# V1.net
KiCad netlist of a schematic drawn in EAGLE
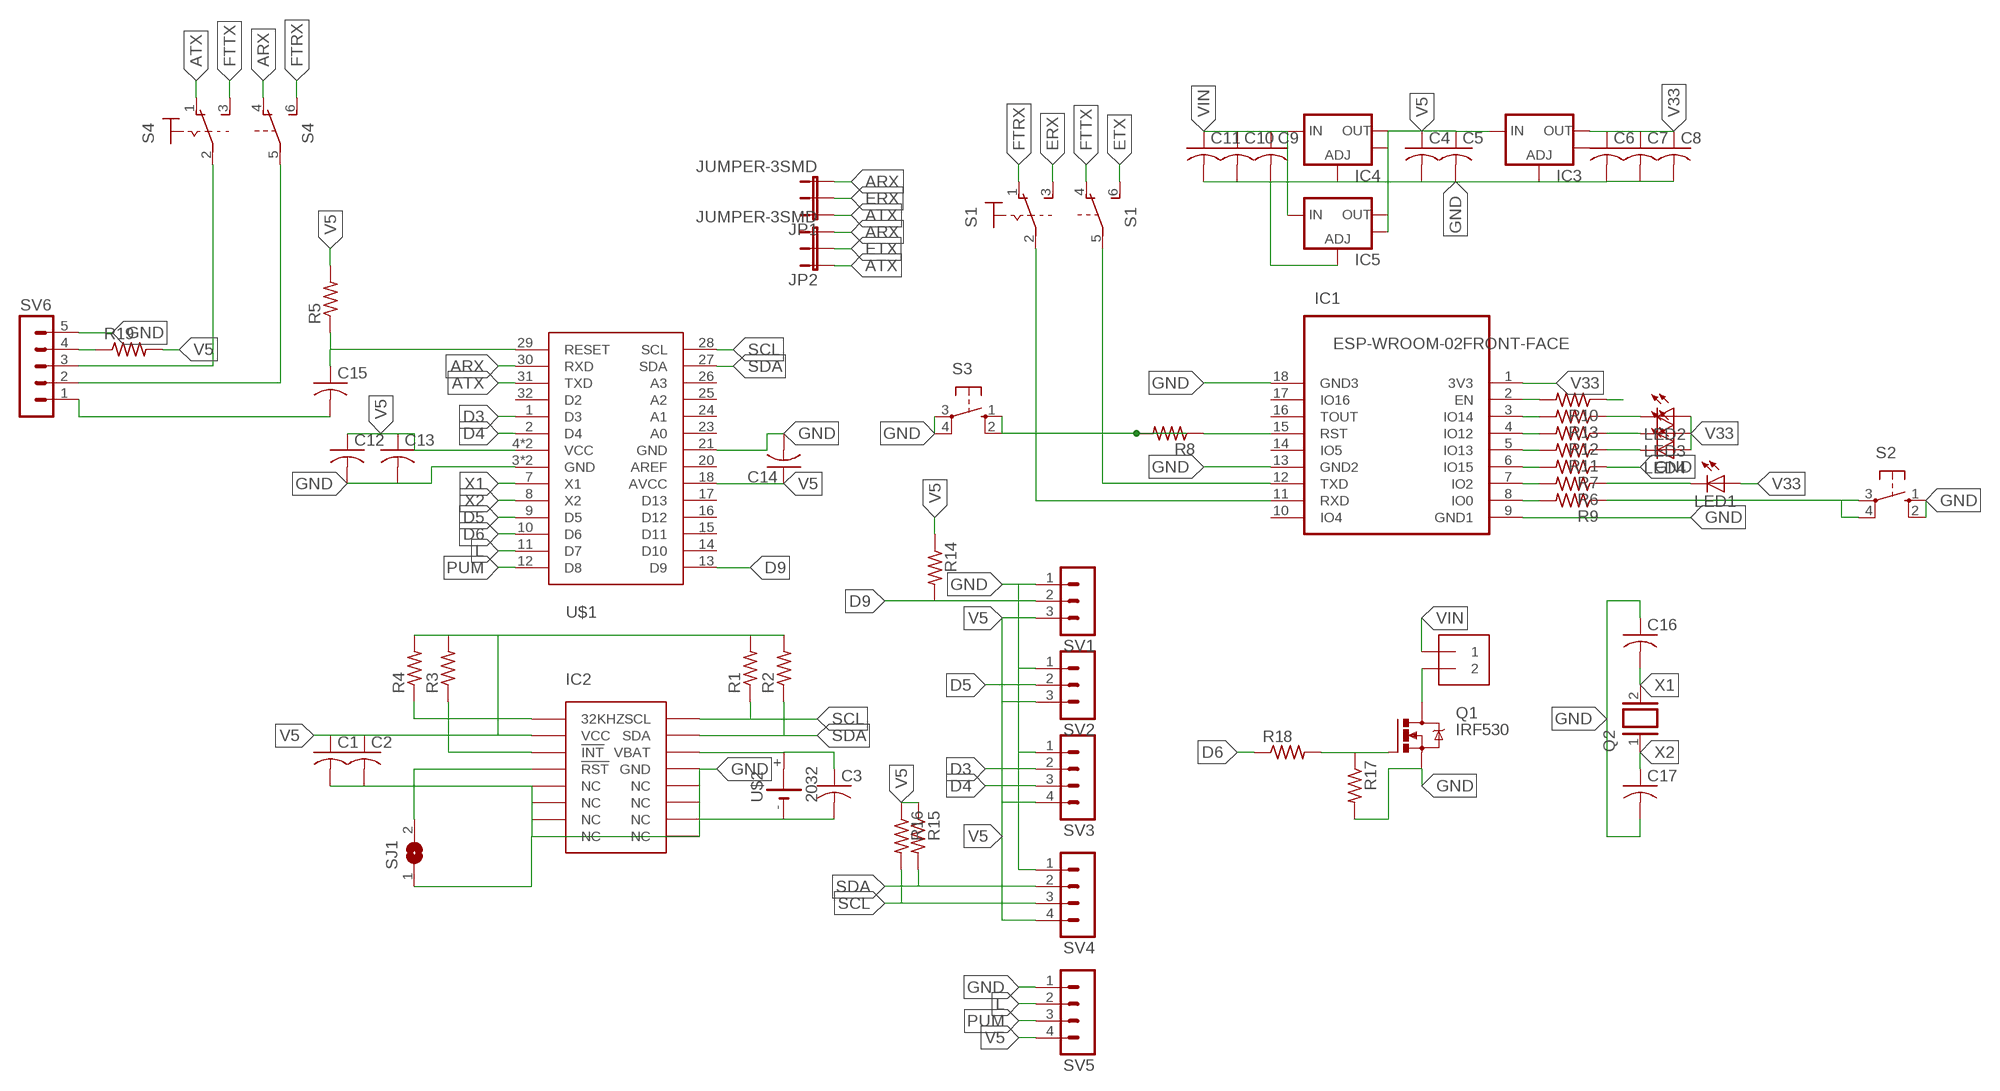
[diagram p0: schematic, sheet 1]

(export (version "E")
  (design (tool "Eeschema 10.0.6"))
  (components
    (comp (ref "C1")
      (value "C-USC0805")
      (footprint "eagle-import:C0805")
      (libsource (lib "eagle-import") (part "C-USC0805"))
    )
    (comp (ref "C2")
      (value "C-USC0805")
      (footprint "eagle-import:C0805")
      (libsource (lib "eagle-import") (part "C-USC0805"))
    )
    (comp (ref "C3")
      (value "C-USC0805")
      (footprint "eagle-import:C0805")
      (libsource (lib "eagle-import") (part "C-USC0805"))
    )
    (comp (ref "C4")
      (value "C-USC0805")
      (footprint "eagle-import:C0805")
      (libsource (lib "eagle-import") (part "C-USC0805"))
    )
    (comp (ref "C5")
      (value "C-USC0805")
      (footprint "eagle-import:C0805")
      (libsource (lib "eagle-import") (part "C-USC0805"))
    )
    (comp (ref "C6")
      (value "C-USC0805")
      (footprint "eagle-import:C0805")
      (libsource (lib "eagle-import") (part "C-USC0805"))
    )
    (comp (ref "C7")
      (value "C-USC0805")
      (footprint "eagle-import:C0805")
      (libsource (lib "eagle-import") (part "C-USC0805"))
    )
    (comp (ref "C8")
      (value "C-USC0805")
      (footprint "eagle-import:C0805")
      (libsource (lib "eagle-import") (part "C-USC0805"))
    )
    (comp (ref "C9")
      (value "C-USC0805")
      (footprint "eagle-import:C0805")
      (libsource (lib "eagle-import") (part "C-USC0805"))
    )
    (comp (ref "C10")
      (value "C-USC0805")
      (footprint "eagle-import:C0805")
      (libsource (lib "eagle-import") (part "C-USC0805"))
    )
    (comp (ref "C11")
      (value "C-USC0805")
      (footprint "eagle-import:C0805")
      (libsource (lib "eagle-import") (part "C-USC0805"))
    )
    (comp (ref "C12")
      (value "C-USC0805")
      (footprint "eagle-import:C0805")
      (libsource (lib "eagle-import") (part "C-USC0805"))
    )
    (comp (ref "C13")
      (value "C-USC0805")
      (footprint "eagle-import:C0805")
      (libsource (lib "eagle-import") (part "C-USC0805"))
    )
    (comp (ref "C14")
      (value "C-USC0805")
      (footprint "eagle-import:C0805")
      (libsource (lib "eagle-import") (part "C-USC0805"))
    )
    (comp (ref "C15")
      (value "C-USC0805")
      (footprint "eagle-import:C0805")
      (libsource (lib "eagle-import") (part "C-USC0805"))
    )
    (comp (ref "C16")
      (value "C-USC0805")
      (footprint "eagle-import:C0805")
      (libsource (lib "eagle-import") (part "C-USC0805"))
    )
    (comp (ref "C17")
      (value "C-USC0805")
      (footprint "eagle-import:C0805")
      (libsource (lib "eagle-import") (part "C-USC0805"))
    )
    (comp (ref "IC1")
      (value "ESP-WROOM-02FRONT-FACE")
      (footprint "eagle-import:FRONT-FACE")
      (libsource (lib "eagle-import") (part "ESP-WROOM-02FRONT-FACE"))
    )
    (comp (ref "IC2")
      (value "DS3231SOIC-16W")
      (footprint "eagle-import:SOIC-16W")
      (libsource (lib "eagle-import") (part "DS3231SOIC-16W"))
    )
    (comp (ref "IC3")
      (value "V_REG_LM1117SOT223")
      (footprint "eagle-import:SOT223")
      (libsource (lib "eagle-import") (part "V_REG_LM1117SOT223"))
    )
    (comp (ref "IC4")
      (value "V_REG_LM1117SOT223")
      (footprint "eagle-import:SOT223")
      (libsource (lib "eagle-import") (part "V_REG_LM1117SOT223"))
    )
    (comp (ref "IC5")
      (value "V_REG_LM1117SOT223")
      (footprint "eagle-import:SOT223")
      (libsource (lib "eagle-import") (part "V_REG_LM1117SOT223"))
    )
    (comp (ref "J1")
      (value "1X2-3.5MM")
      (footprint "eagle-import:3.5MMTERM")
      (libsource (lib "eagle-import") (part "1X2-3.5MM"))
    )
    (comp (ref "JP1")
      (value "JUMPER-3SMD")
      (footprint "eagle-import:SJ_3")
      (libsource (lib "eagle-import") (part "JUMPER-3SMD"))
    )
    (comp (ref "JP2")
      (value "JUMPER-3SMD")
      (footprint "eagle-import:SJ_3")
      (libsource (lib "eagle-import") (part "JUMPER-3SMD"))
    )
    (comp (ref "LED1")
      (value "LED5MM")
      (footprint "eagle-import:LED5MM")
      (libsource (lib "eagle-import") (part "LED5MM"))
    )
    (comp (ref "LED2")
      (value "LED5MM")
      (footprint "eagle-import:LED5MM")
      (libsource (lib "eagle-import") (part "LED5MM"))
    )
    (comp (ref "LED3")
      (value "LED5MM")
      (footprint "eagle-import:LED5MM")
      (libsource (lib "eagle-import") (part "LED5MM"))
    )
    (comp (ref "LED4")
      (value "LED5MM")
      (footprint "eagle-import:LED5MM")
      (libsource (lib "eagle-import") (part "LED5MM"))
    )
    (comp (ref "Q1")
      (value "IRF530")
      (footprint "eagle-import:TO220BV")
      (libsource (lib "eagle-import") (part "IRF530"))
    )
    (comp (ref "Q2")
      (value "XTAL/S")
      (footprint "eagle-import:QS")
      (libsource (lib "eagle-import") (part "XTAL/S"))
    )
    (comp (ref "R1")
      (value "R-US_R0805")
      (footprint "eagle-import:R0805")
      (libsource (lib "eagle-import") (part "R-US_R0805"))
    )
    (comp (ref "R2")
      (value "R-US_R0805")
      (footprint "eagle-import:R0805")
      (libsource (lib "eagle-import") (part "R-US_R0805"))
    )
    (comp (ref "R3")
      (value "R-US_R0805")
      (footprint "eagle-import:R0805")
      (libsource (lib "eagle-import") (part "R-US_R0805"))
    )
    (comp (ref "R4")
      (value "R-US_R0805")
      (footprint "eagle-import:R0805")
      (libsource (lib "eagle-import") (part "R-US_R0805"))
    )
    (comp (ref "R5")
      (value "R-US_R0805")
      (footprint "eagle-import:R0805")
      (libsource (lib "eagle-import") (part "R-US_R0805"))
    )
    (comp (ref "R6")
      (value "R-US_R0805")
      (footprint "eagle-import:R0805")
      (libsource (lib "eagle-import") (part "R-US_R0805"))
    )
    (comp (ref "R7")
      (value "R-US_R0805")
      (footprint "eagle-import:R0805")
      (libsource (lib "eagle-import") (part "R-US_R0805"))
    )
    (comp (ref "R8")
      (value "R-US_R0805")
      (footprint "eagle-import:R0805")
      (libsource (lib "eagle-import") (part "R-US_R0805"))
    )
    (comp (ref "R9")
      (value "R-US_R0805")
      (footprint "eagle-import:R0805")
      (libsource (lib "eagle-import") (part "R-US_R0805"))
    )
    (comp (ref "R10")
      (value "R-US_R0805")
      (footprint "eagle-import:R0805")
      (libsource (lib "eagle-import") (part "R-US_R0805"))
    )
    (comp (ref "R11")
      (value "R-US_R0805")
      (footprint "eagle-import:R0805")
      (libsource (lib "eagle-import") (part "R-US_R0805"))
    )
    (comp (ref "R12")
      (value "R-US_R0805")
      (footprint "eagle-import:R0805")
      (libsource (lib "eagle-import") (part "R-US_R0805"))
    )
    (comp (ref "R13")
      (value "R-US_R0805")
      (footprint "eagle-import:R0805")
      (libsource (lib "eagle-import") (part "R-US_R0805"))
    )
    (comp (ref "R14")
      (value "R-US_R0805")
      (footprint "eagle-import:R0805")
      (libsource (lib "eagle-import") (part "R-US_R0805"))
    )
    (comp (ref "R15")
      (value "R-US_R0805")
      (footprint "eagle-import:R0805")
      (libsource (lib "eagle-import") (part "R-US_R0805"))
    )
    (comp (ref "R16")
      (value "R-US_R0805")
      (footprint "eagle-import:R0805")
      (libsource (lib "eagle-import") (part "R-US_R0805"))
    )
    (comp (ref "R17")
      (value "R-US_R0805")
      (footprint "eagle-import:R0805")
      (libsource (lib "eagle-import") (part "R-US_R0805"))
    )
    (comp (ref "R18")
      (value "R-US_R0805")
      (footprint "eagle-import:R0805")
      (libsource (lib "eagle-import") (part "R-US_R0805"))
    )
    (comp (ref "R19")
      (value "R-US_R0805")
      (footprint "eagle-import:R0805")
      (libsource (lib "eagle-import") (part "R-US_R0805"))
    )
    (comp (ref "S1")
      (value "320-938")
      (footprint "eagle-import:320-938")
      (libsource (lib "eagle-import") (part "320-938"))
    )
    (comp (ref "S2")
      (value "10-XX")
      (footprint "eagle-import:B3F-10XX")
      (fields (field (name "MPN") "B3F-1000"))
      (libsource (lib "eagle-import") (part "10-XX"))
    )
    (comp (ref "S3")
      (value "10-XX")
      (footprint "eagle-import:B3F-10XX")
      (fields (field (name "MPN") "B3F-1000"))
      (libsource (lib "eagle-import") (part "10-XX"))
    )
    (comp (ref "S4")
      (value "320-938")
      (footprint "eagle-import:320-938")
      (libsource (lib "eagle-import") (part "320-938"))
    )
    (comp (ref "SJ1")
      (value "SJW")
      (footprint "eagle-import:SJW")
      (libsource (lib "eagle-import") (part "SJW"))
    )
    (comp (ref "SV1")
      (value "MA03-1")
      (footprint "eagle-import:MA03-1")
      (libsource (lib "eagle-import") (part "MA03-1"))
    )
    (comp (ref "SV2")
      (value "MA03-1")
      (footprint "eagle-import:MA03-1")
      (libsource (lib "eagle-import") (part "MA03-1"))
    )
    (comp (ref "SV3")
      (value "MA04-1")
      (footprint "eagle-import:MA04-1")
      (libsource (lib "eagle-import") (part "MA04-1"))
    )
    (comp (ref "SV4")
      (value "MA04-1")
      (footprint "eagle-import:MA04-1")
      (libsource (lib "eagle-import") (part "MA04-1"))
    )
    (comp (ref "SV5")
      (value "MA04-1")
      (footprint "eagle-import:MA04-1")
      (libsource (lib "eagle-import") (part "MA04-1"))
    )
    (comp (ref "SV6")
      (value "MA05-1")
      (footprint "eagle-import:MA05-1")
      (libsource (lib "eagle-import") (part "MA05-1"))
    )
    (comp (ref "U$1")
      (value "ATMEGA328P")
      (footprint "eagle-import:TQFP32-08")
      (libsource (lib "eagle-import") (part "ATMEGA328P"))
    )
    (comp (ref "U$2")
      (value "2032")
      (footprint "eagle-import:KZH20SMD")
      (libsource (lib "eagle-import") (part "2032"))
    )
  )
  (nets
    (net (code "1") (name "ARX") (class "Default")
      (node (ref "C15") (pin "1") (pinfunction "1_1") (pintype "passive"))
      (node (ref "JP1") (pin "3") (pinfunction "3_3") (pintype "passive"))
      (node (ref "JP2") (pin "3") (pinfunction "3_3") (pintype "passive"))
      (node (ref "R5") (pin "1") (pinfunction "1_1") (pintype "passive"))
      (node (ref "S4") (pin "4") (pinfunction "O_4") (pintype "passive"))
      (node (ref "U$1") (pin "29") (pinfunction "RESET_29") (pintype "bidirectional"))
      (node (ref "U$1") (pin "30") (pinfunction "RXD_30") (pintype "bidirectional"))
    )
    (net (code "2") (name "ATX") (class "Default")
      (node (ref "JP1") (pin "1") (pinfunction "1_1") (pintype "passive"))
      (node (ref "JP2") (pin "1") (pinfunction "1_1") (pintype "passive"))
      (node (ref "S4") (pin "1") (pinfunction "O_1") (pintype "passive"))
      (node (ref "U$1") (pin "31") (pinfunction "TXD_31") (pintype "bidirectional"))
    )
    (net (code "3") (name "D3") (class "Default")
      (node (ref "SV3") (pin "2") (pinfunction "2_2") (pintype "passive"))
      (node (ref "U$1") (pin "1") (pinfunction "D3_1") (pintype "bidirectional"))
    )
    (net (code "4") (name "D4") (class "Default")
      (node (ref "SV3") (pin "3") (pinfunction "3_3") (pintype "passive"))
      (node (ref "U$1") (pin "2") (pinfunction "D4_2") (pintype "bidirectional"))
    )
    (net (code "5") (name "D5") (class "Default")
      (node (ref "SV2") (pin "2") (pinfunction "2_2") (pintype "passive"))
      (node (ref "U$1") (pin "9") (pinfunction "D5_9") (pintype "bidirectional"))
    )
    (net (code "6") (name "D6") (class "Default")
      (node (ref "R18") (pin "1") (pinfunction "1_1") (pintype "passive"))
      (node (ref "U$1") (pin "10") (pinfunction "D6_10") (pintype "bidirectional"))
    )
    (net (code "7") (name "D9") (class "Default")
      (node (ref "R14") (pin "2") (pinfunction "2_2") (pintype "passive"))
      (node (ref "SV1") (pin "2") (pinfunction "2_2") (pintype "passive"))
      (node (ref "U$1") (pin "13") (pinfunction "D9_13") (pintype "bidirectional"))
    )
    (net (code "8") (name "ERX") (class "Default")
      (node (ref "JP1") (pin "2") (pinfunction "2_2") (pintype "passive"))
      (node (ref "S1") (pin "3") (pinfunction "S_3") (pintype "passive"))
    )
    (net (code "9") (name "ETX") (class "Default")
      (node (ref "JP2") (pin "2") (pinfunction "2_2") (pintype "passive"))
      (node (ref "S1") (pin "6") (pinfunction "S_6") (pintype "passive"))
    )
    (net (code "10") (name "FTRX") (class "Default")
      (node (ref "S1") (pin "1") (pinfunction "O_1") (pintype "passive"))
      (node (ref "S4") (pin "6") (pinfunction "S_6") (pintype "passive"))
    )
    (net (code "11") (name "FTTX") (class "Default")
      (node (ref "S1") (pin "4") (pinfunction "O_4") (pintype "passive"))
      (node (ref "S4") (pin "3") (pinfunction "S_3") (pintype "passive"))
    )
    (net (code "12") (name "GND") (class "Default")
      (node (ref "C1") (pin "2") (pinfunction "2_2") (pintype "passive"))
      (node (ref "C10") (pin "2") (pinfunction "2_2") (pintype "passive"))
      (node (ref "C11") (pin "2") (pinfunction "2_2") (pintype "passive"))
      (node (ref "C12") (pin "2") (pinfunction "2_2") (pintype "passive"))
      (node (ref "C13") (pin "2") (pinfunction "2_2") (pintype "passive"))
      (node (ref "C14") (pin "2") (pinfunction "2_2") (pintype "passive"))
      (node (ref "C16") (pin "1") (pinfunction "1_1") (pintype "passive"))
      (node (ref "C17") (pin "2") (pinfunction "2_2") (pintype "passive"))
      (node (ref "C2") (pin "2") (pinfunction "2_2") (pintype "passive"))
      (node (ref "C3") (pin "2") (pinfunction "2_2") (pintype "passive"))
      (node (ref "C4") (pin "2") (pinfunction "2_2") (pintype "passive"))
      (node (ref "C5") (pin "2") (pinfunction "2_2") (pintype "passive"))
      (node (ref "C6") (pin "2") (pinfunction "2_2") (pintype "passive"))
      (node (ref "C7") (pin "2") (pinfunction "2_2") (pintype "passive"))
      (node (ref "C8") (pin "2") (pinfunction "2_2") (pintype "passive"))
      (node (ref "C9") (pin "2") (pinfunction "2_2") (pintype "passive"))
      (node (ref "IC1") (pin "13") (pinfunction "GND2_13") (pintype "power_in"))
      (node (ref "IC1") (pin "18") (pinfunction "GND3_18") (pintype "power_in"))
      (node (ref "IC1") (pin "9") (pinfunction "GND1_9") (pintype "power_in"))
      (node (ref "IC2") (pin "10") (pinfunction "NC_10") (pintype "bidirectional"))
      (node (ref "IC2") (pin "11") (pinfunction "NC_11") (pintype "bidirectional"))
      (node (ref "IC2") (pin "12") (pinfunction "NC_12") (pintype "bidirectional"))
      (node (ref "IC2") (pin "13") (pinfunction "GND_13") (pintype "bidirectional"))
      (node (ref "IC2") (pin "5") (pinfunction "NC_5") (pintype "bidirectional"))
      (node (ref "IC2") (pin "6") (pinfunction "NC_6") (pintype "bidirectional"))
      (node (ref "IC2") (pin "7") (pinfunction "NC_7") (pintype "bidirectional"))
      (node (ref "IC2") (pin "8") (pinfunction "NC_8") (pintype "bidirectional"))
      (node (ref "IC2") (pin "9") (pinfunction "NC_9") (pintype "bidirectional"))
      (node (ref "IC3") (pin "1") (pinfunction "ADJ_1") (pintype "input"))
      (node (ref "IC4") (pin "1") (pinfunction "ADJ_1") (pintype "input"))
      (node (ref "IC5") (pin "1") (pinfunction "ADJ_1") (pintype "input"))
      (node (ref "Q1") (pin "S") (pinfunction "S_S") (pintype "passive"))
      (node (ref "R17") (pin "2") (pinfunction "2_2") (pintype "passive"))
      (node (ref "R7") (pin "1") (pinfunction "1_1") (pintype "passive"))
      (node (ref "S2") (pin "1") (pinfunction "S_1") (pintype "passive"))
      (node (ref "S2") (pin "2") (pinfunction "S1_2") (pintype "passive"))
      (node (ref "S3") (pin "3") (pinfunction "P_3") (pintype "passive"))
      (node (ref "S3") (pin "4") (pinfunction "P1_4") (pintype "passive"))
      (node (ref "SJ1") (pin "1") (pinfunction "1_1") (pintype "passive"))
      (node (ref "SV1") (pin "1") (pinfunction "1_1") (pintype "passive"))
      (node (ref "SV2") (pin "1") (pinfunction "1_1") (pintype "passive"))
      (node (ref "SV3") (pin "1") (pinfunction "1_1") (pintype "passive"))
      (node (ref "SV4") (pin "1") (pinfunction "1_1") (pintype "passive"))
      (node (ref "SV5") (pin "1") (pinfunction "1_1") (pintype "passive"))
      (node (ref "SV6") (pin "5") (pinfunction "5_5") (pintype "passive"))
      (node (ref "U$1") (pin "21") (pinfunction "GND_21") (pintype "bidirectional"))
      (node (ref "U$1") (pin "3") (pinfunction "GND_3") (pintype "bidirectional"))
      (node (ref "U$1") (pin "5") (pinfunction "GND_5") (pintype "bidirectional"))
      (node (ref "U$2") (pin "-") (pinfunction "-_-") (pintype "passive"))
    )
    (net (code "13") (name "L") (class "Default")
      (node (ref "SV5") (pin "2") (pinfunction "2_2") (pintype "passive"))
      (node (ref "U$1") (pin "11") (pinfunction "D7_11") (pintype "bidirectional"))
    )
    (net (code "14") (name "Net-(C15-Pad2)") (class "Default")
      (node (ref "C15") (pin "2") (pinfunction "2_2") (pintype "passive"))
      (node (ref "SV6") (pin "1") (pinfunction "1_1") (pintype "passive"))
    )
    (net (code "15") (name "Net-(IC1-EN)") (class "Default")
      (node (ref "IC1") (pin "2") (pinfunction "EN_2") (pintype "bidirectional"))
      (node (ref "R10") (pin "2") (pinfunction "2_2") (pintype "passive"))
    )
    (net (code "16") (name "Net-(IC1-IO0)") (class "Default")
      (node (ref "IC1") (pin "8") (pinfunction "IO0_8") (pintype "bidirectional"))
      (node (ref "R9") (pin "2") (pinfunction "2_2") (pintype "passive"))
    )
    (net (code "17") (name "Net-(IC1-IO2)") (class "Default")
      (node (ref "IC1") (pin "7") (pinfunction "IO2_7") (pintype "bidirectional"))
      (node (ref "R6") (pin "2") (pinfunction "2_2") (pintype "passive"))
    )
    (net (code "18") (name "Net-(IC1-IO12)") (class "Default")
      (node (ref "IC1") (pin "4") (pinfunction "IO12_4") (pintype "bidirectional"))
      (node (ref "R12") (pin "2") (pinfunction "2_2") (pintype "passive"))
    )
    (net (code "19") (name "Net-(IC1-IO13)") (class "Default")
      (node (ref "IC1") (pin "5") (pinfunction "IO13_5") (pintype "bidirectional"))
      (node (ref "R11") (pin "2") (pinfunction "2_2") (pintype "passive"))
    )
    (net (code "20") (name "Net-(IC1-IO14)") (class "Default")
      (node (ref "IC1") (pin "3") (pinfunction "IO14_3") (pintype "bidirectional"))
      (node (ref "R13") (pin "2") (pinfunction "2_2") (pintype "passive"))
    )
    (net (code "21") (name "Net-(IC1-IO15)") (class "Default")
      (node (ref "IC1") (pin "6") (pinfunction "IO15_6") (pintype "bidirectional"))
      (node (ref "R7") (pin "2") (pinfunction "2_2") (pintype "passive"))
    )
    (net (code "22") (name "Net-(IC1-RST)") (class "Default")
      (node (ref "IC1") (pin "15") (pinfunction "RST_15") (pintype "bidirectional"))
      (node (ref "R8") (pin "1") (pinfunction "1_1") (pintype "passive"))
    )
    (net (code "23") (name "Net-(IC1-RXD)") (class "Default")
      (node (ref "IC1") (pin "11") (pinfunction "RXD_11") (pintype "bidirectional"))
      (node (ref "S1") (pin "2") (pinfunction "P_2") (pintype "passive"))
    )
    (net (code "24") (name "Net-(IC1-TXD)") (class "Default")
      (node (ref "IC1") (pin "12") (pinfunction "TXD_12") (pintype "bidirectional"))
      (node (ref "S1") (pin "5") (pinfunction "P_5") (pintype "passive"))
    )
    (net (code "25") (name "Net-(IC2-32KHZ)") (class "Default")
      (node (ref "IC2") (pin "1") (pinfunction "32KHZ_1") (pintype "bidirectional"))
      (node (ref "R4") (pin "1") (pinfunction "1_1") (pintype "passive"))
    )
    (net (code "26") (name "Net-(IC2-VBAT)") (class "Default")
      (node (ref "C3") (pin "1") (pinfunction "1_1") (pintype "passive"))
      (node (ref "IC2") (pin "14") (pinfunction "VBAT_14") (pintype "bidirectional"))
      (node (ref "U$2") (pin "+") (pinfunction "+_+") (pintype "passive"))
    )
    (net (code "27") (name "Net-(IC2-~{INT})") (class "Default")
      (node (ref "IC2") (pin "3") (pinfunction "~{INT}_3") (pintype "bidirectional"))
      (node (ref "R3") (pin "1") (pinfunction "1_1") (pintype "passive"))
    )
    (net (code "28") (name "Net-(IC2-~{RST})") (class "Default")
      (node (ref "IC2") (pin "4") (pinfunction "~{RST}_4") (pintype "bidirectional"))
      (node (ref "SJ1") (pin "2") (pinfunction "2_2") (pintype "passive"))
    )
    (net (code "29") (name "Net-(J1-Pad2)") (class "Default")
      (node (ref "J1") (pin "2") (pinfunction "2_2") (pintype "passive"))
      (node (ref "Q1") (pin "D") (pinfunction "D_D") (pintype "passive"))
    )
    (net (code "30") (name "Net-(LED2-C)") (class "Default")
      (node (ref "LED2") (pin "K") (pinfunction "C_K") (pintype "passive"))
      (node (ref "R13") (pin "1") (pinfunction "1_1") (pintype "passive"))
    )
    (net (code "31") (name "Net-(LED3-C)") (class "Default")
      (node (ref "LED3") (pin "K") (pinfunction "C_K") (pintype "passive"))
      (node (ref "R12") (pin "1") (pinfunction "1_1") (pintype "passive"))
    )
    (net (code "32") (name "Net-(LED4-C)") (class "Default")
      (node (ref "LED4") (pin "K") (pinfunction "C_K") (pintype "passive"))
      (node (ref "R11") (pin "1") (pinfunction "1_1") (pintype "passive"))
    )
    (net (code "33") (name "Net-(Q1-PadG)") (class "Default")
      (node (ref "Q1") (pin "G") (pinfunction "G_G") (pintype "passive"))
      (node (ref "R17") (pin "1") (pinfunction "1_1") (pintype "passive"))
      (node (ref "R18") (pin "2") (pinfunction "2_2") (pintype "passive"))
    )
    (net (code "34") (name "Net-(R19-Pad1)") (class "Default")
      (node (ref "R19") (pin "1") (pinfunction "1_1") (pintype "passive"))
      (node (ref "SV6") (pin "4") (pinfunction "4_4") (pintype "passive"))
    )
    (net (code "35") (name "Net-(S2-P)") (class "Default")
      (node (ref "R9") (pin "1") (pinfunction "1_1") (pintype "passive"))
      (node (ref "S2") (pin "3") (pinfunction "P_3") (pintype "passive"))
      (node (ref "S2") (pin "4") (pinfunction "P1_4") (pintype "passive"))
    )
    (net (code "36") (name "Net-(S3-S)") (class "Default")
      (node (ref "R8") (pin "2") (pinfunction "2_2") (pintype "passive"))
      (node (ref "S3") (pin "1") (pinfunction "S_1") (pintype "passive"))
      (node (ref "S3") (pin "2") (pinfunction "S1_2") (pintype "passive"))
    )
    (net (code "37") (name "Net-(S4A-P)") (class "Default")
      (node (ref "S4") (pin "2") (pinfunction "P_2") (pintype "passive"))
      (node (ref "SV6") (pin "3") (pinfunction "3_3") (pintype "passive"))
    )
    (net (code "38") (name "Net-(S4B-P)") (class "Default")
      (node (ref "S4") (pin "5") (pinfunction "P_5") (pintype "passive"))
      (node (ref "SV6") (pin "2") (pinfunction "2_2") (pintype "passive"))
    )
    (net (code "39") (name "PUM") (class "Default")
      (node (ref "SV5") (pin "3") (pinfunction "3_3") (pintype "passive"))
      (node (ref "U$1") (pin "12") (pinfunction "D8_12") (pintype "bidirectional"))
    )
    (net (code "40") (name "SCL") (class "Default")
      (node (ref "IC2") (pin "16") (pinfunction "SCL_16") (pintype "bidirectional"))
      (node (ref "R1") (pin "1") (pinfunction "1_1") (pintype "passive"))
      (node (ref "R16") (pin "2") (pinfunction "2_2") (pintype "passive"))
      (node (ref "SV4") (pin "3") (pinfunction "3_3") (pintype "passive"))
      (node (ref "U$1") (pin "28") (pinfunction "SCL_28") (pintype "bidirectional"))
    )
    (net (code "41") (name "SDA") (class "Default")
      (node (ref "IC2") (pin "15") (pinfunction "SDA_15") (pintype "bidirectional"))
      (node (ref "R15") (pin "2") (pinfunction "2_2") (pintype "passive"))
      (node (ref "R2") (pin "1") (pinfunction "1_1") (pintype "passive"))
      (node (ref "SV4") (pin "2") (pinfunction "2_2") (pintype "passive"))
      (node (ref "U$1") (pin "27") (pinfunction "SDA_27") (pintype "bidirectional"))
    )
    (net (code "42") (name "V5") (class "Default")
      (node (ref "C1") (pin "1") (pinfunction "1_1") (pintype "passive"))
      (node (ref "C12") (pin "1") (pinfunction "1_1") (pintype "passive"))
      (node (ref "C13") (pin "1") (pinfunction "1_1") (pintype "passive"))
      (node (ref "C14") (pin "1") (pinfunction "1_1") (pintype "passive"))
      (node (ref "C2") (pin "1") (pinfunction "1_1") (pintype "passive"))
      (node (ref "C4") (pin "1") (pinfunction "1_1") (pintype "passive"))
      (node (ref "C5") (pin "1") (pinfunction "1_1") (pintype "passive"))
      (node (ref "IC2") (pin "2") (pinfunction "VCC_2") (pintype "bidirectional"))
      (node (ref "IC3") (pin "3") (pinfunction "IN_3") (pintype "input"))
      (node (ref "IC4") (pin "2") (pinfunction "OUT_2") (pintype "output"))
      (node (ref "IC4") (pin "4") (pinfunction "OUT_4") (pintype "output"))
      (node (ref "IC5") (pin "2") (pinfunction "OUT_2") (pintype "output"))
      (node (ref "IC5") (pin "4") (pinfunction "OUT_4") (pintype "output"))
      (node (ref "R1") (pin "2") (pinfunction "2_2") (pintype "passive"))
      (node (ref "R14") (pin "1") (pinfunction "1_1") (pintype "passive"))
      (node (ref "R15") (pin "1") (pinfunction "1_1") (pintype "passive"))
      (node (ref "R16") (pin "1") (pinfunction "1_1") (pintype "passive"))
      (node (ref "R19") (pin "2") (pinfunction "2_2") (pintype "passive"))
      (node (ref "R2") (pin "2") (pinfunction "2_2") (pintype "passive"))
      (node (ref "R3") (pin "2") (pinfunction "2_2") (pintype "passive"))
      (node (ref "R4") (pin "2") (pinfunction "2_2") (pintype "passive"))
      (node (ref "R5") (pin "2") (pinfunction "2_2") (pintype "passive"))
      (node (ref "SV1") (pin "3") (pinfunction "3_3") (pintype "passive"))
      (node (ref "SV2") (pin "3") (pinfunction "3_3") (pintype "passive"))
      (node (ref "SV3") (pin "4") (pinfunction "4_4") (pintype "passive"))
      (node (ref "SV4") (pin "4") (pinfunction "4_4") (pintype "passive"))
      (node (ref "SV5") (pin "4") (pinfunction "4_4") (pintype "passive"))
      (node (ref "U$1") (pin "18") (pinfunction "AVCC_18") (pintype "bidirectional"))
      (node (ref "U$1") (pin "4") (pinfunction "VCC_4") (pintype "bidirectional"))
      (node (ref "U$1") (pin "6") (pinfunction "VCC_6") (pintype "bidirectional"))
    )
    (net (code "43") (name "V33") (class "Default")
      (node (ref "C6") (pin "1") (pinfunction "1_1") (pintype "passive"))
      (node (ref "C7") (pin "1") (pinfunction "1_1") (pintype "passive"))
      (node (ref "C8") (pin "1") (pinfunction "1_1") (pintype "passive"))
      (node (ref "IC1") (pin "1") (pinfunction "3V3_1") (pintype "power_in"))
      (node (ref "IC3") (pin "2") (pinfunction "OUT_2") (pintype "output"))
      (node (ref "LED1") (pin "A") (pinfunction "A_A") (pintype "passive"))
      (node (ref "LED1") (pin "K") (pinfunction "C_K") (pintype "passive"))
      (node (ref "LED2") (pin "A") (pinfunction "A_A") (pintype "passive"))
      (node (ref "LED3") (pin "A") (pinfunction "A_A") (pintype "passive"))
      (node (ref "LED4") (pin "A") (pinfunction "A_A") (pintype "passive"))
      (node (ref "R6") (pin "1") (pinfunction "1_1") (pintype "passive"))
    )
    (net (code "44") (name "VIN") (class "Default")
      (node (ref "C10") (pin "1") (pinfunction "1_1") (pintype "passive"))
      (node (ref "C11") (pin "1") (pinfunction "1_1") (pintype "passive"))
      (node (ref "C9") (pin "1") (pinfunction "1_1") (pintype "passive"))
      (node (ref "IC4") (pin "3") (pinfunction "IN_3") (pintype "input"))
      (node (ref "IC5") (pin "3") (pinfunction "IN_3") (pintype "input"))
      (node (ref "J1") (pin "1") (pinfunction "1_1") (pintype "passive"))
    )
    (net (code "45") (name "X1") (class "Default")
      (node (ref "C16") (pin "2") (pinfunction "2_2") (pintype "passive"))
      (node (ref "Q2") (pin "2") (pinfunction "2_2") (pintype "passive"))
      (node (ref "U$1") (pin "7") (pinfunction "X1_7") (pintype "bidirectional"))
    )
    (net (code "46") (name "X2") (class "Default")
      (node (ref "C17") (pin "1") (pinfunction "1_1") (pintype "passive"))
      (node (ref "Q2") (pin "1") (pinfunction "1_1") (pintype "passive"))
      (node (ref "U$1") (pin "8") (pinfunction "X2_8") (pintype "bidirectional"))
    )
    (net (code "47") (name "unconnected-(IC1-IO4-Pad10)") (class "Default")
      (node (ref "IC1") (pin "10") (pinfunction "IO4_10") (pintype "bidirectional"))
    )
    (net (code "48") (name "unconnected-(IC1-IO5-Pad14)") (class "Default")
      (node (ref "IC1") (pin "14") (pinfunction "IO5_14") (pintype "open_collector"))
    )
    (net (code "49") (name "unconnected-(IC1-IO16-Pad17)") (class "Default")
      (node (ref "IC1") (pin "17") (pinfunction "IO16_17") (pintype "bidirectional"))
    )
    (net (code "50") (name "unconnected-(IC1-TOUT-Pad16)") (class "Default")
      (node (ref "IC1") (pin "16") (pinfunction "TOUT_16") (pintype "bidirectional"))
    )
    (net (code "51") (name "unconnected-(IC3-OUT-Pad4)") (class "Default")
      (node (ref "IC3") (pin "4") (pinfunction "OUT_4") (pintype "output"))
    )
    (net (code "52") (name "unconnected-(R10-Pad1)") (class "Default")
      (node (ref "R10") (pin "1") (pinfunction "1_1") (pintype "passive"))
    )
    (net (code "53") (name "unconnected-(U$1-A0-Pad23)") (class "Default")
      (node (ref "U$1") (pin "23") (pinfunction "A0_23") (pintype "bidirectional"))
    )
    (net (code "54") (name "unconnected-(U$1-A1-Pad24)") (class "Default")
      (node (ref "U$1") (pin "24") (pinfunction "A1_24") (pintype "bidirectional"))
    )
    (net (code "55") (name "unconnected-(U$1-A2-Pad25)") (class "Default")
      (node (ref "U$1") (pin "25") (pinfunction "A2_25") (pintype "bidirectional"))
    )
    (net (code "56") (name "unconnected-(U$1-A3-Pad26)") (class "Default")
      (node (ref "U$1") (pin "26") (pinfunction "A3_26") (pintype "bidirectional"))
    )
    (net (code "57") (name "unconnected-(U$1-AREF-Pad20)") (class "Default")
      (node (ref "U$1") (pin "20") (pinfunction "AREF_20") (pintype "bidirectional"))
    )
    (net (code "58") (name "unconnected-(U$1-D2-Pad32)") (class "Default")
      (node (ref "U$1") (pin "32") (pinfunction "D2_32") (pintype "bidirectional"))
    )
    (net (code "59") (name "unconnected-(U$1-D10-Pad14)") (class "Default")
      (node (ref "U$1") (pin "14") (pinfunction "D10_14") (pintype "bidirectional"))
    )
    (net (code "60") (name "unconnected-(U$1-D11-Pad15)") (class "Default")
      (node (ref "U$1") (pin "15") (pinfunction "D11_15") (pintype "bidirectional"))
    )
    (net (code "61") (name "unconnected-(U$1-D12-Pad16)") (class "Default")
      (node (ref "U$1") (pin "16") (pinfunction "D12_16") (pintype "bidirectional"))
    )
    (net (code "62") (name "unconnected-(U$1-D13-Pad17)") (class "Default")
      (node (ref "U$1") (pin "17") (pinfunction "D13_17") (pintype "bidirectional"))
    )
  )
)
